# AD8065_circuit.net
KiCad netlist of a schematic drawn in Altium Designer
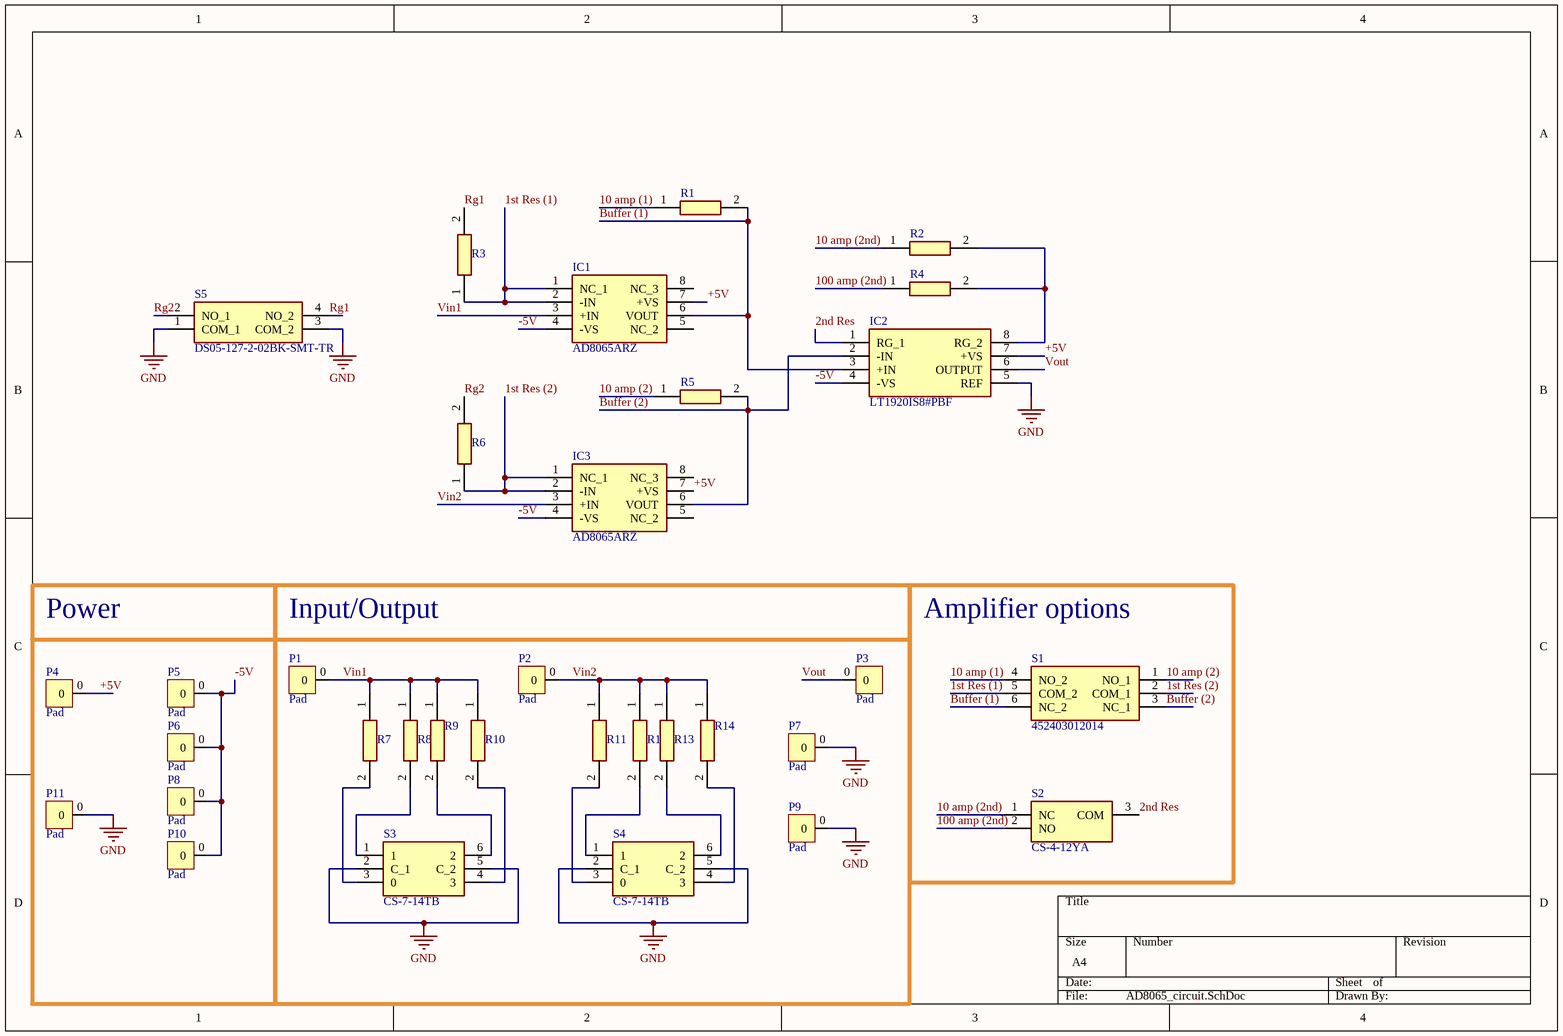
[diagram p0: AD8065_circuit.SchDoc]

(export (version "E")
  (design (tool "Eeschema 10.0.6"))
  (components
    (comp (ref "IC1")
      (value "AD8065ARZ")
      (footprint "SamacSys:SOIC127P600X175-8N")
      (description "Integrated Circuit")
      (fields (field (name "MOUSER PART NUMBER") "584-AD8065ARZ"))
      (libsource (lib "SamacSys") (part "AD8065ARZ"))
    )
    (comp (ref "IC2")
      (value "LT1920IS8#PBF")
      (footprint "SamacSys:SOIC127P599X175-8N")
      (description "Integrated Circuit")
      (fields (field (name "MOUSER PART NUMBER") "584-LT1920IS8#PBF"))
      (libsource (lib "SamacSys") (part "LT1920IS8#PBF"))
    )
    (comp (ref "IC3")
      (value "AD8065ARZ")
      (footprint "SamacSys:SOIC127P600X175-8N")
      (description "Integrated Circuit")
      (fields (field (name "MOUSER PART NUMBER") "584-AD8065ARZ"))
      (libsource (lib "SamacSys") (part "AD8065ARZ"))
    )
    (comp (ref "P1") (value "Pad") (footprint "Pad") (libsource (lib "SamacSys") (part "Pad")))
    (comp (ref "P2") (value "Pad") (footprint "Pad") (libsource (lib "SamacSys") (part "Pad")))
    (comp (ref "P3") (value "Pad") (footprint "Pad") (libsource (lib "") (part "Pad_1")))
    (comp (ref "P4") (value "Pad") (footprint "Pad") (libsource (lib "SamacSys") (part "Pad")))
    (comp (ref "P5") (value "Pad") (footprint "Pad") (libsource (lib "SamacSys") (part "Pad")))
    (comp (ref "P6") (value "Pad") (footprint "Pad") (libsource (lib "SamacSys") (part "Pad")))
    (comp (ref "P7") (value "Pad") (footprint "Pad") (libsource (lib "SamacSys") (part "Pad")))
    (comp (ref "P8") (value "Pad") (footprint "Pad") (libsource (lib "SamacSys") (part "Pad")))
    (comp (ref "P9") (value "Pad") (footprint "Pad") (libsource (lib "SamacSys") (part "Pad")))
    (comp (ref "P10") (value "Pad") (footprint "Pad") (libsource (lib "SamacSys") (part "Pad")))
    (comp (ref "P11") (value "Pad") (footprint "Pad") (libsource (lib "SamacSys") (part "Pad")))
    (comp (ref "R1")
      (value "CRG0805F270R")
      (footprint "SamacSys:RESC2012X65N")
      (description "Resistor 270")
      (fields (field (name "MOUSER PART NUMBER") "279-CRG0805F270R"))
      (libsource (lib "*") (part "CRG0805F270R"))
    )
    (comp (ref "R2")
      (value "CRG0805F4K7")
      (footprint "SamacSys:RESC2012X65N")
      (description "Resistor 4.7k")
      (fields (field (name "MOUSER PART NUMBER") "279-CRG0805F4K7"))
      (libsource (lib "*") (part "CRG0805F4K7"))
    )
    (comp (ref "R3")
      (value "CRGH0805F20R")
      (footprint "SamacSys:RESC2013X65N")
      (description "Resistor 20")
      (fields (field (name "MOUSER PART NUMBER") "279-CRGH0805F20R"))
      (libsource (lib "*") (part "CRGH0805F20R"))
    )
    (comp (ref "R4")
      (value "CRG0805F330R")
      (footprint "SamacSys:RESC2012X65N")
      (description "Resistor 330")
      (fields (field (name "MOUSER PART NUMBER") "279-CRG0805F330R"))
      (libsource (lib "*") (part "CRG0805F330R"))
    )
    (comp (ref "R5")
      (value "CRG0805F270R")
      (footprint "SamacSys:RESC2012X65N")
      (description "Resistor 270")
      (fields (field (name "MOUSER PART NUMBER") "279-CRG0805F270R"))
      (libsource (lib "*") (part "CRG0805F270R"))
    )
    (comp (ref "R6")
      (value "CRGH0805F20R")
      (footprint "SamacSys:RESC2013X65N")
      (description "Resistor 20")
      (fields (field (name "MOUSER PART NUMBER") "279-CRGH0805F20R"))
      (libsource (lib "*") (part "CRGH0805F20R"))
    )
    (comp (ref "R7")
      (value "RH73X2A10GNTN")
      (footprint "SamacSys:RESC2013X50N")
      (description "Resistor 10G")
      (fields (field (name "MOUSER PART NUMBER") "279-RH73X2A10GNTN"))
      (libsource (lib "*") (part "RH73X2A10GNTN"))
    )
    (comp (ref "R8")
      (value "RH73X2A50GNTN")
      (footprint "SamacSys:RESC2013X50N")
      (description "Resistor 50G")
      (fields (field (name "MOUSER PART NUMBER") "279-RH73X2A50GNTN"))
      (libsource (lib "*") (part "RH73X2A50GNTN"))
    )
    (comp (ref "R9")
      (value "RH73H2A100MKTN")
      (footprint "SamacSys:RESC2013X50N")
      (description "Resistor 100M")
      (fields (field (name "MOUSER PART NUMBER") "279-RH73H2A100MKTN"))
      (libsource (lib "*") (part "RH73H2A100MKTN"))
    )
    (comp (ref "R10")
      (value "RH73W2A1GNTN")
      (footprint "SamacSys:RESC2013X50N")
      (description "Resistor 1G")
      (fields (field (name "MOUSER PART NUMBER") "279-RH73W2A1GNTN"))
      (libsource (lib "*") (part "RH73W2A1GNTN"))
    )
    (comp (ref "R11")
      (value "RH73X2A50GNTN")
      (footprint "SamacSys:RESC2013X50N")
      (description "Resistor 50G")
      (fields (field (name "MOUSER PART NUMBER") "279-RH73X2A50GNTN"))
      (libsource (lib "*") (part "RH73X2A50GNTN"))
    )
    (comp (ref "R12")
      (value "RH73X2A10GNTN")
      (footprint "SamacSys:RESC2013X50N")
      (description "Resistor 10G")
      (fields (field (name "MOUSER PART NUMBER") "279-RH73X2A10GNTN"))
      (libsource (lib "*") (part "RH73X2A10GNTN"))
    )
    (comp (ref "R13")
      (value "RH73W2A1GNTN")
      (footprint "SamacSys:RESC2013X50N")
      (description "Resistor 1G")
      (fields (field (name "MOUSER PART NUMBER") "279-RH73W2A1GNTN"))
      (libsource (lib "*") (part "RH73W2A1GNTN"))
    )
    (comp (ref "R14")
      (value "RH73H2A100MKTN")
      (footprint "SamacSys:RESC2013X50N")
      (description "Resistor 100M")
      (fields (field (name "MOUSER PART NUMBER") "279-RH73H2A100MKTN"))
      (libsource (lib "*") (part "RH73H2A100MKTN"))
    )
    (comp (ref "S1")
      (value "452403012014")
      (footprint "SamacSys:452403012014")
      (description "Switch")
      (fields (field (name "MOUSER PART NUMBER") "710-452403012014"))
      (libsource (lib "SamacSys") (part "452403012014"))
    )
    (comp (ref "S2")
      (value "CS-4-12YA")
      (footprint "SamacSys:CS412YA")
      (description "Switch")
      (libsource (lib "SamacSys") (part "CS-4-12YA"))
    )
    (comp (ref "S3")
      (value "CS-7-14TB")
      (footprint "SamacSys:SOP254P1000X405-6N")
      (description "Switch")
      (libsource (lib "*") (part "CS-7-14TB"))
    )
    (comp (ref "S4")
      (value "CS-7-14TB")
      (footprint "SamacSys:SOP254P1000X405-6N")
      (description "Switch")
      (libsource (lib "*") (part "CS-7-14TB"))
    )
    (comp (ref "S5")
      (value "DS05-127-2-02BK-SMT-TR")
      (footprint "SamacSys:DS05127202BKSMTTR")
      (description "Switch")
      (fields (field (name "MOUSER PART NUMBER") "490-DS05127202BK-STR"))
      (libsource (lib "*") (part "DS05-127-2-02BK-SMT-TR"))
    )
  )
  (nets
    (net (code "1") (name "/+5V") (class "Default")
      (node (ref "IC1") (pin "7") (pinfunction "+VS_7") (pintype "passive"))
      (node (ref "IC2") (pin "7") (pinfunction "+VS_7") (pintype "passive"))
      (node (ref "IC3") (pin "7") (pinfunction "+VS_7") (pintype "passive"))
      (node (ref "P4") (pin "0") (pinfunction "0_0") (pintype "passive"))
    )
    (net (code "2") (name "/-5V") (class "Default")
      (node (ref "IC1") (pin "4") (pinfunction "-VS_4") (pintype "passive"))
      (node (ref "IC2") (pin "4") (pinfunction "-VS_4") (pintype "passive"))
      (node (ref "IC3") (pin "4") (pinfunction "-VS_4") (pintype "passive"))
      (node (ref "P10") (pin "0") (pinfunction "0_0") (pintype "passive"))
      (node (ref "P5") (pin "0") (pinfunction "0_0") (pintype "passive"))
      (node (ref "P6") (pin "0") (pinfunction "0_0") (pintype "passive"))
      (node (ref "P8") (pin "0") (pinfunction "0_0") (pintype "passive"))
    )
    (net (code "3") (name "/1st Res (1)") (class "Default")
      (node (ref "IC1") (pin "1") (pinfunction "NC_1_1") (pintype "passive"))
      (node (ref "IC1") (pin "2") (pinfunction "-IN_2") (pintype "passive"))
      (node (ref "R3") (pin "1") (pinfunction "1_1") (pintype "passive"))
      (node (ref "S1") (pin "5") (pinfunction "COM_2_5") (pintype "passive"))
    )
    (net (code "4") (name "/1st Res (2)") (class "Default")
      (node (ref "IC3") (pin "1") (pinfunction "NC_1_1") (pintype "passive"))
      (node (ref "IC3") (pin "2") (pinfunction "-IN_2") (pintype "passive"))
      (node (ref "R6") (pin "1") (pinfunction "1_1") (pintype "passive"))
      (node (ref "S1") (pin "2") (pinfunction "COM_1_2") (pintype "passive"))
    )
    (net (code "5") (name "/2nd Res") (class "Default")
      (node (ref "IC2") (pin "1") (pinfunction "RG_1_1") (pintype "passive"))
      (node (ref "S2") (pin "3") (pinfunction "COM_3") (pintype "passive"))
    )
    (net (code "6") (name "/10 amp (1)") (class "Default")
      (node (ref "R1") (pin "1") (pinfunction "1_1") (pintype "passive"))
      (node (ref "S1") (pin "4") (pinfunction "NO_2_4") (pintype "passive"))
    )
    (net (code "7") (name "/10 amp (2)") (class "Default")
      (node (ref "R5") (pin "1") (pinfunction "1_1") (pintype "passive"))
      (node (ref "S1") (pin "1") (pinfunction "NO_1_1") (pintype "passive"))
    )
    (net (code "8") (name "/10 amp (2nd)") (class "Default")
      (node (ref "R2") (pin "1") (pinfunction "1_1") (pintype "passive"))
      (node (ref "S2") (pin "1") (pinfunction "NC_1") (pintype "passive"))
    )
    (net (code "9") (name "/100 amp (2nd)") (class "Default")
      (node (ref "R4") (pin "1") (pinfunction "1_1") (pintype "passive"))
      (node (ref "S2") (pin "2") (pinfunction "NO_2") (pintype "passive"))
    )
    (net (code "10") (name "/Buffer (1)") (class "Default")
      (node (ref "IC1") (pin "6") (pinfunction "VOUT_6") (pintype "passive"))
      (node (ref "IC2") (pin "3") (pinfunction "+IN_3") (pintype "passive"))
      (node (ref "R1") (pin "2") (pinfunction "2_2") (pintype "passive"))
      (node (ref "S1") (pin "6") (pinfunction "NC_2_6") (pintype "passive"))
    )
    (net (code "11") (name "/Buffer (2)") (class "Default")
      (node (ref "IC2") (pin "2") (pinfunction "-IN_2") (pintype "passive"))
      (node (ref "IC3") (pin "6") (pinfunction "VOUT_6") (pintype "passive"))
      (node (ref "R5") (pin "2") (pinfunction "2_2") (pintype "passive"))
      (node (ref "S1") (pin "3") (pinfunction "NC_1_3") (pintype "passive"))
    )
    (net (code "12") (name "/Rg1") (class "Default")
      (node (ref "R3") (pin "2") (pinfunction "2_2") (pintype "passive"))
      (node (ref "S5") (pin "4") (pinfunction "NO_2_4") (pintype "passive"))
    )
    (net (code "13") (name "/Rg2") (class "Default")
      (node (ref "R6") (pin "2") (pinfunction "2_2") (pintype "passive"))
      (node (ref "S5") (pin "2") (pinfunction "NO_1_2") (pintype "passive"))
    )
    (net (code "14") (name "/Vin1") (class "Default")
      (node (ref "IC1") (pin "3") (pinfunction "+IN_3") (pintype "passive"))
      (node (ref "P1") (pin "0") (pinfunction "0_0") (pintype "passive"))
      (node (ref "R10") (pin "1") (pinfunction "1_1") (pintype "passive"))
      (node (ref "R7") (pin "1") (pinfunction "1_1") (pintype "passive"))
      (node (ref "R8") (pin "1") (pinfunction "1_1") (pintype "passive"))
      (node (ref "R9") (pin "1") (pinfunction "1_1") (pintype "passive"))
    )
    (net (code "15") (name "/Vin2") (class "Default")
      (node (ref "IC3") (pin "3") (pinfunction "+IN_3") (pintype "passive"))
      (node (ref "P2") (pin "0") (pinfunction "0_0") (pintype "passive"))
      (node (ref "R11") (pin "1") (pinfunction "1_1") (pintype "passive"))
      (node (ref "R12") (pin "1") (pinfunction "1_1") (pintype "passive"))
      (node (ref "R13") (pin "1") (pinfunction "1_1") (pintype "passive"))
      (node (ref "R14") (pin "1") (pinfunction "1_1") (pintype "passive"))
    )
    (net (code "16") (name "/Vout") (class "Default")
      (node (ref "IC2") (pin "6") (pinfunction "OUTPUT_6") (pintype "passive"))
      (node (ref "P3") (pin "0") (pinfunction "0_0") (pintype "passive"))
    )
    (net (code "17") (name "GND") (class "Default")
      (node (ref "IC2") (pin "5") (pinfunction "REF_5") (pintype "passive"))
      (node (ref "P11") (pin "0") (pinfunction "0_0") (pintype "passive"))
      (node (ref "P7") (pin "0") (pinfunction "0_0") (pintype "passive"))
      (node (ref "P9") (pin "0") (pinfunction "0_0") (pintype "passive"))
      (node (ref "S3") (pin "2") (pinfunction "C_1_2") (pintype "passive"))
      (node (ref "S3") (pin "5") (pinfunction "C_2_5") (pintype "passive"))
      (node (ref "S4") (pin "2") (pinfunction "C_1_2") (pintype "passive"))
      (node (ref "S4") (pin "5") (pinfunction "C_2_5") (pintype "passive"))
      (node (ref "S5") (pin "1") (pinfunction "COM_1_1") (pintype "passive"))
      (node (ref "S5") (pin "3") (pinfunction "COM_2_3") (pintype "passive"))
    )
    (net (code "18") (name "Net-(IC2-RG_2)") (class "Default")
      (node (ref "IC2") (pin "8") (pinfunction "RG_2_8") (pintype "passive"))
      (node (ref "R2") (pin "2") (pinfunction "2_2") (pintype "passive"))
      (node (ref "R4") (pin "2") (pinfunction "2_2") (pintype "passive"))
    )
    (net (code "19") (name "Net-(R8-Pad2)") (class "Default")
      (node (ref "R8") (pin "2") (pinfunction "2_2") (pintype "passive"))
      (node (ref "S3") (pin "1") (pinfunction "1_1") (pintype "passive"))
    )
    (net (code "20") (name "Net-(R12-Pad2)") (class "Default")
      (node (ref "R12") (pin "2") (pinfunction "2_2") (pintype "passive"))
      (node (ref "S4") (pin "1") (pinfunction "1_1") (pintype "passive"))
    )
    (net (code "21") (name "Net-(S3-0)") (class "Default")
      (node (ref "R7") (pin "2") (pinfunction "2_2") (pintype "passive"))
      (node (ref "S3") (pin "3") (pinfunction "0_3") (pintype "passive"))
    )
    (net (code "22") (name "Net-(S3-2)") (class "Default")
      (node (ref "R9") (pin "2") (pinfunction "2_2") (pintype "passive"))
      (node (ref "S3") (pin "6") (pinfunction "2_6") (pintype "passive"))
    )
    (net (code "23") (name "Net-(S3-3)") (class "Default")
      (node (ref "R10") (pin "2") (pinfunction "2_2") (pintype "passive"))
      (node (ref "S3") (pin "4") (pinfunction "3_4") (pintype "passive"))
    )
    (net (code "24") (name "Net-(S4-0)") (class "Default")
      (node (ref "R11") (pin "2") (pinfunction "2_2") (pintype "passive"))
      (node (ref "S4") (pin "3") (pinfunction "0_3") (pintype "passive"))
    )
    (net (code "25") (name "Net-(S4-2)") (class "Default")
      (node (ref "R13") (pin "2") (pinfunction "2_2") (pintype "passive"))
      (node (ref "S4") (pin "6") (pinfunction "2_6") (pintype "passive"))
    )
    (net (code "26") (name "Net-(S4-3)") (class "Default")
      (node (ref "R14") (pin "2") (pinfunction "2_2") (pintype "passive"))
      (node (ref "S4") (pin "4") (pinfunction "3_4") (pintype "passive"))
    )
    (net (code "27") (name "unconnected-(IC1-NC_2-Pad5)") (class "Default")
      (node (ref "IC1") (pin "5") (pinfunction "NC_2_5") (pintype "passive"))
    )
    (net (code "28") (name "unconnected-(IC1-NC_3-Pad8)") (class "Default")
      (node (ref "IC1") (pin "8") (pinfunction "NC_3_8") (pintype "passive"))
    )
    (net (code "29") (name "unconnected-(IC3-NC_2-Pad5)") (class "Default")
      (node (ref "IC3") (pin "5") (pinfunction "NC_2_5") (pintype "passive"))
    )
    (net (code "30") (name "unconnected-(IC3-NC_3-Pad8)") (class "Default")
      (node (ref "IC3") (pin "8") (pinfunction "NC_3_8") (pintype "passive"))
    )
  )
)
